# Mind-Synchronizing-Generator-PinHdrPot.net
KiCad netlist of a schematic drawn in EAGLE
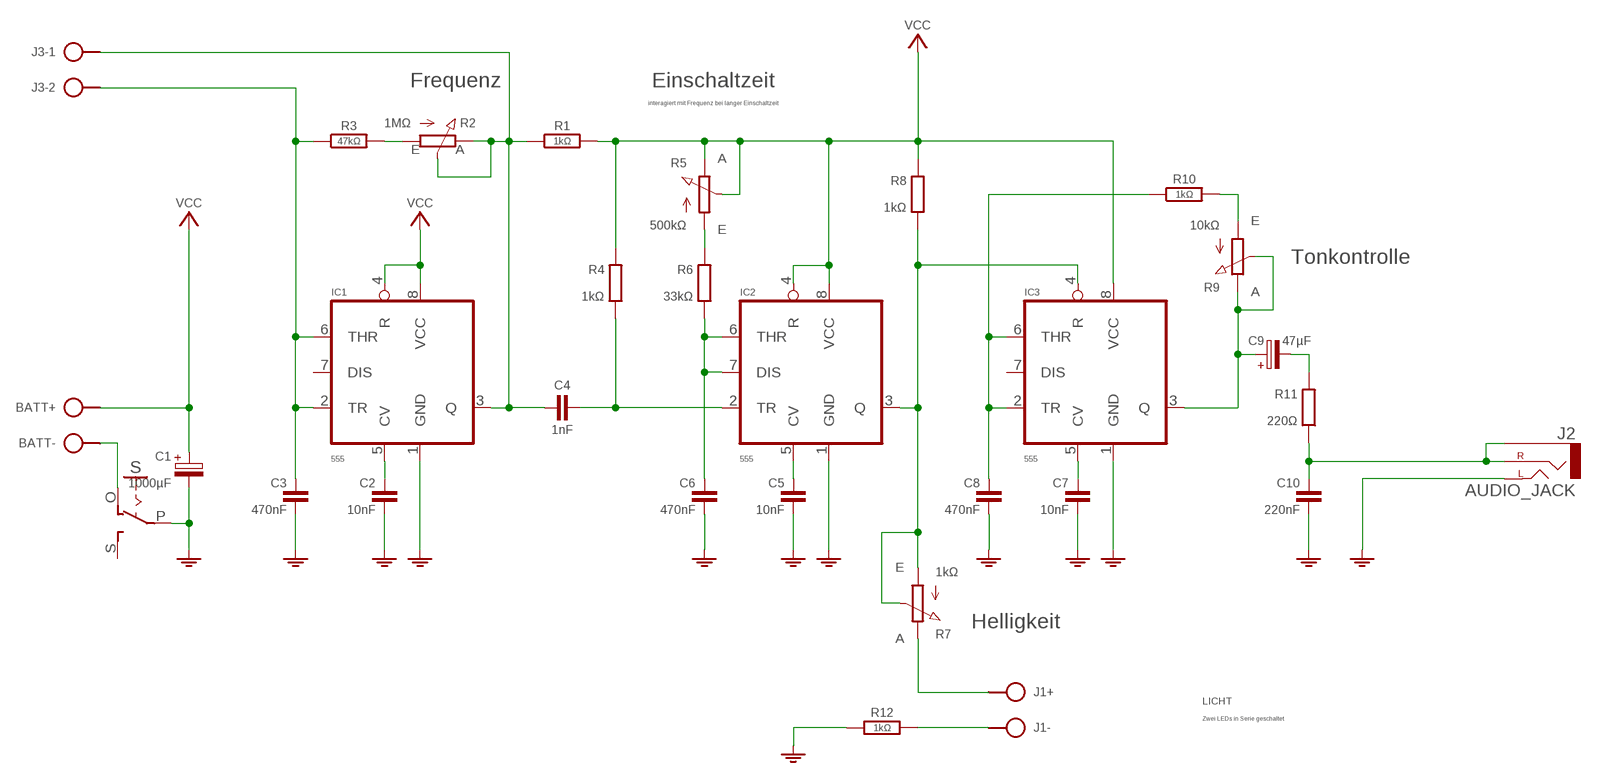
[diagram p0: schematic, sheet 1]

(export (version "E")
  (design (tool "Eeschema 10.0.6"))
  (components
    (comp (ref "BATT")
      (value "SPAD+--+")
      (footprint "eagle-import:SPAD-+")
      (libsource (lib "eagle-import") (part "SPAD+--+"))
    )
    (comp (ref "C1")
      (value "1000µF")
      (footprint "eagle-import:E5-8,5")
      (libsource (lib "eagle-import") (part "CPOLE5-8.5"))
    )
    (comp (ref "C2")
      (value "10nF")
      (footprint "eagle-import:C050-020X044")
      (libsource (lib "eagle-import") (part "C050-020X044"))
    )
    (comp (ref "C3")
      (value "470nF")
      (footprint "eagle-import:C050-040X075")
      (libsource (lib "eagle-import") (part "C050-040X075"))
    )
    (comp (ref "C4")
      (value "1nF")
      (footprint "eagle-import:C050-020X044")
      (libsource (lib "eagle-import") (part "C-H050-020X044"))
    )
    (comp (ref "C5")
      (value "10nF")
      (footprint "eagle-import:C050-020X044_V")
      (libsource (lib "eagle-import") (part "C050-020X044/V"))
    )
    (comp (ref "C6")
      (value "470nF")
      (footprint "eagle-import:C050-040X075")
      (libsource (lib "eagle-import") (part "C050-040X075"))
    )
    (comp (ref "C7")
      (value "10nF")
      (footprint "eagle-import:C075-020X044_V")
      (libsource (lib "eagle-import") (part "C075-020X044/V"))
    )
    (comp (ref "C8")
      (value "470nF")
      (footprint "eagle-import:C050-040X075")
      (libsource (lib "eagle-import") (part "C050-040X075"))
    )
    (comp (ref "C9")
      (value "47µF")
      (footprint "eagle-import:E2,5-4")
      (libsource (lib "eagle-import") (part "CPOL-HE2,5-4"))
    )
    (comp (ref "C10")
      (value "220nF")
      (footprint "eagle-import:C050-025X060")
      (libsource (lib "eagle-import") (part "C025-025X060"))
    )
    (comp (ref "IC1")
      (value "555")
      (footprint "eagle-import:555-DIL")
      (libsource (lib "eagle-import") (part "555_ALT2-LBL"))
    )
    (comp (ref "IC2")
      (value "555")
      (footprint "eagle-import:555-DIL")
      (libsource (lib "eagle-import") (part "555_ALT2-LBL"))
    )
    (comp (ref "IC3")
      (value "555")
      (footprint "eagle-import:555-DIL")
      (libsource (lib "eagle-import") (part "555_ALT2-LBL"))
    )
    (comp (ref "J1")
      (value "SPAD+--+")
      (footprint "eagle-import:SPAD-+")
      (libsource (lib "eagle-import") (part "SPAD+--+"))
    )
    (comp (ref "J2")
      (value "AUDIO_JACK")
      (footprint "eagle-import:AUDIO-JACK")
      (libsource (lib "eagle-import") (part "AUDIO_JACK"))
    )
    (comp (ref "J3")
      (value "SPAD-2")
      (footprint "eagle-import:SPAD-2")
      (libsource (lib "eagle-import") (part "SPAD-2"))
    )
    (comp (ref "R1")
      (value "1kΩ")
      (footprint "eagle-import:0204_10")
      (libsource (lib "eagle-import") (part "R-H0204/10"))
    )
    (comp (ref "R2")
      (value "1MΩ")
      (footprint "eagle-import:CONN-3P")
      (libsource (lib "eagle-import") (part "POT-H-3P"))
    )
    (comp (ref "R3")
      (value "47kΩ")
      (footprint "eagle-import:0204_10")
      (libsource (lib "eagle-import") (part "R-H0204/10"))
    )
    (comp (ref "R4")
      (value "1kΩ")
      (footprint "eagle-import:0204_10-V")
      (libsource (lib "eagle-import") (part "R0204/10-V"))
    )
    (comp (ref "R5")
      (value "500kΩ")
      (footprint "eagle-import:CONN-3P")
      (libsource (lib "eagle-import") (part "POT-3P"))
    )
    (comp (ref "R6")
      (value "33kΩ")
      (footprint "eagle-import:0204_10")
      (libsource (lib "eagle-import") (part "R0204/10"))
    )
    (comp (ref "R7")
      (value "1kΩ")
      (footprint "eagle-import:CONN-3P")
      (libsource (lib "eagle-import") (part "POT-3P"))
    )
    (comp (ref "R8")
      (value "1kΩ")
      (footprint "eagle-import:0204_10-V")
      (libsource (lib "eagle-import") (part "R0204/10-V"))
    )
    (comp (ref "R9")
      (value "10kΩ")
      (footprint "eagle-import:CONN-3P")
      (libsource (lib "eagle-import") (part "POT-3P"))
    )
    (comp (ref "R10")
      (value "1kΩ")
      (footprint "eagle-import:0204_10")
      (libsource (lib "eagle-import") (part "R-H0204/10"))
    )
    (comp (ref "R11")
      (value "220Ω")
      (footprint "eagle-import:0204_10-V")
      (libsource (lib "eagle-import") (part "R0204/10-V"))
    )
    (comp (ref "R12")
      (value "1kΩ")
      (footprint "eagle-import:0204_10")
      (libsource (lib "eagle-import") (part "R-H0204/10"))
    )
    (comp (ref "S")
      (value "SL-SW-1P-2T-H")
      (footprint "eagle-import:SLSW-1P2T-H")
      (libsource (lib "eagle-import") (part "SL-SW-1P-2T-H"))
    )
  )
  (nets
    (net (code "1") (name "GND") (class "Default")
      (node (ref "C1") (pin "-") (pinfunction "-_-") (pintype "passive"))
      (node (ref "C10") (pin "2") (pinfunction "2_2") (pintype "passive"))
      (node (ref "C2") (pin "2") (pinfunction "2_2") (pintype "passive"))
      (node (ref "C3") (pin "2") (pinfunction "2_2") (pintype "passive"))
      (node (ref "C5") (pin "2") (pinfunction "2_2") (pintype "passive"))
      (node (ref "C6") (pin "2") (pinfunction "2_2") (pintype "passive"))
      (node (ref "C7") (pin "2") (pinfunction "2_2") (pintype "passive"))
      (node (ref "C8") (pin "2") (pinfunction "2_2") (pintype "passive"))
      (node (ref "IC1") (pin "1") (pinfunction "GND_1") (pintype "power_in"))
      (node (ref "IC2") (pin "1") (pinfunction "GND_1") (pintype "power_in"))
      (node (ref "IC3") (pin "1") (pinfunction "GND_1") (pintype "power_in"))
      (node (ref "J2") (pin "TIP") (pinfunction "LEFT_TIP") (pintype "bidirectional"))
      (node (ref "R12") (pin "1") (pinfunction "1_1") (pintype "passive"))
      (node (ref "S") (pin "P") (pinfunction "P_P") (pintype "passive"))
    )
    (net (code "2") (name "Net-(BATTB-P$1)") (class "Default")
      (node (ref "BATT") (pin "1") (pinfunction "P$1_1") (pintype "passive"))
      (node (ref "S") (pin "O") (pinfunction "O_O") (pintype "passive"))
    )
    (net (code "3") (name "Net-(IC1-CV)") (class "Default")
      (node (ref "C2") (pin "1") (pinfunction "1_1") (pintype "passive"))
      (node (ref "IC1") (pin "5") (pinfunction "CV_5") (pintype "input"))
    )
    (net (code "4") (name "Net-(IC1-Q)") (class "Default")
      (node (ref "C4") (pin "1") (pinfunction "1_1") (pintype "passive"))
      (node (ref "IC1") (pin "3") (pinfunction "Q_3") (pintype "output"))
      (node (ref "J3") (pin "1") (pinfunction "P$1_1") (pintype "passive"))
      (node (ref "R1") (pin "1") (pinfunction "1_1") (pintype "passive"))
      (node (ref "R2") (pin "2") (pinfunction "S_2") (pintype "passive"))
      (node (ref "R2") (pin "3") (pinfunction "E_3") (pintype "passive"))
    )
    (net (code "5") (name "Net-(IC1-THR)") (class "Default")
      (node (ref "C3") (pin "1") (pinfunction "1_1") (pintype "passive"))
      (node (ref "IC1") (pin "2") (pinfunction "TR_2") (pintype "input"))
      (node (ref "IC1") (pin "6") (pinfunction "THR_6") (pintype "input"))
      (node (ref "J3") (pin "2") (pinfunction "P$1_2") (pintype "passive"))
      (node (ref "R3") (pin "1") (pinfunction "1_1") (pintype "passive"))
    )
    (net (code "6") (name "Net-(IC2-CV)") (class "Default")
      (node (ref "C5") (pin "1") (pinfunction "1_1") (pintype "passive"))
      (node (ref "IC2") (pin "5") (pinfunction "CV_5") (pintype "input"))
    )
    (net (code "7") (name "Net-(IC2-DIS)") (class "Default")
      (node (ref "C6") (pin "1") (pinfunction "1_1") (pintype "passive"))
      (node (ref "IC2") (pin "6") (pinfunction "THR_6") (pintype "input"))
      (node (ref "IC2") (pin "7") (pinfunction "DIS_7") (pintype "passive"))
      (node (ref "R6") (pin "2") (pinfunction "1_2") (pintype "passive"))
    )
    (net (code "8") (name "Net-(IC2-Q)") (class "Default")
      (node (ref "IC2") (pin "3") (pinfunction "Q_3") (pintype "output"))
      (node (ref "IC3") (pin "4") (pinfunction "R_4") (pintype "input"))
      (node (ref "R7") (pin "1") (pinfunction "A_1") (pintype "passive"))
      (node (ref "R7") (pin "2") (pinfunction "S_2") (pintype "passive"))
      (node (ref "R8") (pin "2") (pinfunction "1_2") (pintype "passive"))
    )
    (net (code "9") (name "Net-(IC2-TR)") (class "Default")
      (node (ref "C4") (pin "2") (pinfunction "2_2") (pintype "passive"))
      (node (ref "IC2") (pin "2") (pinfunction "TR_2") (pintype "input"))
      (node (ref "R4") (pin "2") (pinfunction "1_2") (pintype "passive"))
    )
    (net (code "10") (name "Net-(IC3-CV)") (class "Default")
      (node (ref "C7") (pin "1") (pinfunction "1_1") (pintype "passive"))
      (node (ref "IC3") (pin "5") (pinfunction "CV_5") (pintype "input"))
    )
    (net (code "11") (name "Net-(IC3-Q)") (class "Default")
      (node (ref "C9") (pin "+") (pinfunction "+_+") (pintype "passive"))
      (node (ref "IC3") (pin "3") (pinfunction "Q_3") (pintype "output"))
      (node (ref "R9") (pin "2") (pinfunction "S_2") (pintype "passive"))
      (node (ref "R9") (pin "3") (pinfunction "E_3") (pintype "passive"))
    )
    (net (code "12") (name "Net-(IC3-THR)") (class "Default")
      (node (ref "C8") (pin "1") (pinfunction "1_1") (pintype "passive"))
      (node (ref "IC3") (pin "2") (pinfunction "TR_2") (pintype "input"))
      (node (ref "IC3") (pin "6") (pinfunction "THR_6") (pintype "input"))
      (node (ref "R10") (pin "1") (pinfunction "1_1") (pintype "passive"))
    )
    (net (code "13") (name "Net-(J1A-P$1)") (class "Default")
      (node (ref "J1") (pin "2") (pinfunction "P$1_2") (pintype "passive"))
      (node (ref "R7") (pin "3") (pinfunction "E_3") (pintype "passive"))
    )
    (net (code "14") (name "Net-(J1B-P$1)") (class "Default")
      (node (ref "J1") (pin "1") (pinfunction "P$1_1") (pintype "passive"))
      (node (ref "R12") (pin "2") (pinfunction "2_2") (pintype "passive"))
    )
    (net (code "15") (name "Net-(J2-RIGHT)") (class "Default")
      (node (ref "C10") (pin "1") (pinfunction "1_1") (pintype "passive"))
      (node (ref "J2") (pin "RING") (pinfunction "RIGHT_RING") (pintype "bidirectional"))
      (node (ref "J2") (pin "SLEEVE") (pinfunction "SLEEVE_SLEEVE") (pintype "bidirectional"))
      (node (ref "R11") (pin "2") (pinfunction "1_2") (pintype "passive"))
    )
    (net (code "16") (name "Net-(R2-A)") (class "Default")
      (node (ref "R2") (pin "1") (pinfunction "A_1") (pintype "passive"))
      (node (ref "R3") (pin "2") (pinfunction "2_2") (pintype "passive"))
    )
    (net (code "17") (name "Net-(R5-A)") (class "Default")
      (node (ref "R5") (pin "1") (pinfunction "A_1") (pintype "passive"))
      (node (ref "R6") (pin "1") (pinfunction "2_1") (pintype "passive"))
    )
    (net (code "18") (name "Net-(R9-A)") (class "Default")
      (node (ref "R10") (pin "2") (pinfunction "2_2") (pintype "passive"))
      (node (ref "R9") (pin "1") (pinfunction "A_1") (pintype "passive"))
    )
    (net (code "19") (name "Net-(R11-2)") (class "Default")
      (node (ref "C9") (pin "-") (pinfunction "-_-") (pintype "passive"))
      (node (ref "R11") (pin "1") (pinfunction "2_1") (pintype "passive"))
    )
    (net (code "20") (name "VCC") (class "Default")
      (node (ref "BATT") (pin "2") (pinfunction "P$1_2") (pintype "passive"))
      (node (ref "C1") (pin "+") (pinfunction "+_+") (pintype "passive"))
      (node (ref "IC1") (pin "4") (pinfunction "R_4") (pintype "input"))
      (node (ref "IC1") (pin "8") (pinfunction "VCC_8") (pintype "power_in"))
      (node (ref "IC2") (pin "4") (pinfunction "R_4") (pintype "input"))
      (node (ref "IC2") (pin "8") (pinfunction "VCC_8") (pintype "power_in"))
      (node (ref "IC3") (pin "8") (pinfunction "VCC_8") (pintype "power_in"))
      (node (ref "R1") (pin "2") (pinfunction "2_2") (pintype "passive"))
      (node (ref "R4") (pin "1") (pinfunction "2_1") (pintype "passive"))
      (node (ref "R5") (pin "2") (pinfunction "S_2") (pintype "passive"))
      (node (ref "R5") (pin "3") (pinfunction "E_3") (pintype "passive"))
      (node (ref "R8") (pin "1") (pinfunction "2_1") (pintype "passive"))
    )
    (net (code "21") (name "unconnected-(IC1-DIS-Pad7)") (class "Default")
      (node (ref "IC1") (pin "7") (pinfunction "DIS_7") (pintype "passive"))
    )
    (net (code "22") (name "unconnected-(IC3-DIS-Pad7)") (class "Default")
      (node (ref "IC3") (pin "7") (pinfunction "DIS_7") (pintype "passive"))
    )
    (net (code "23") (name "unconnected-(S-PadS)") (class "Default")
      (node (ref "S") (pin "S") (pinfunction "S_S") (pintype "passive"))
    )
  )
)
